# AES50.net
KiCad netlist of a schematic drawn in Altium Designer
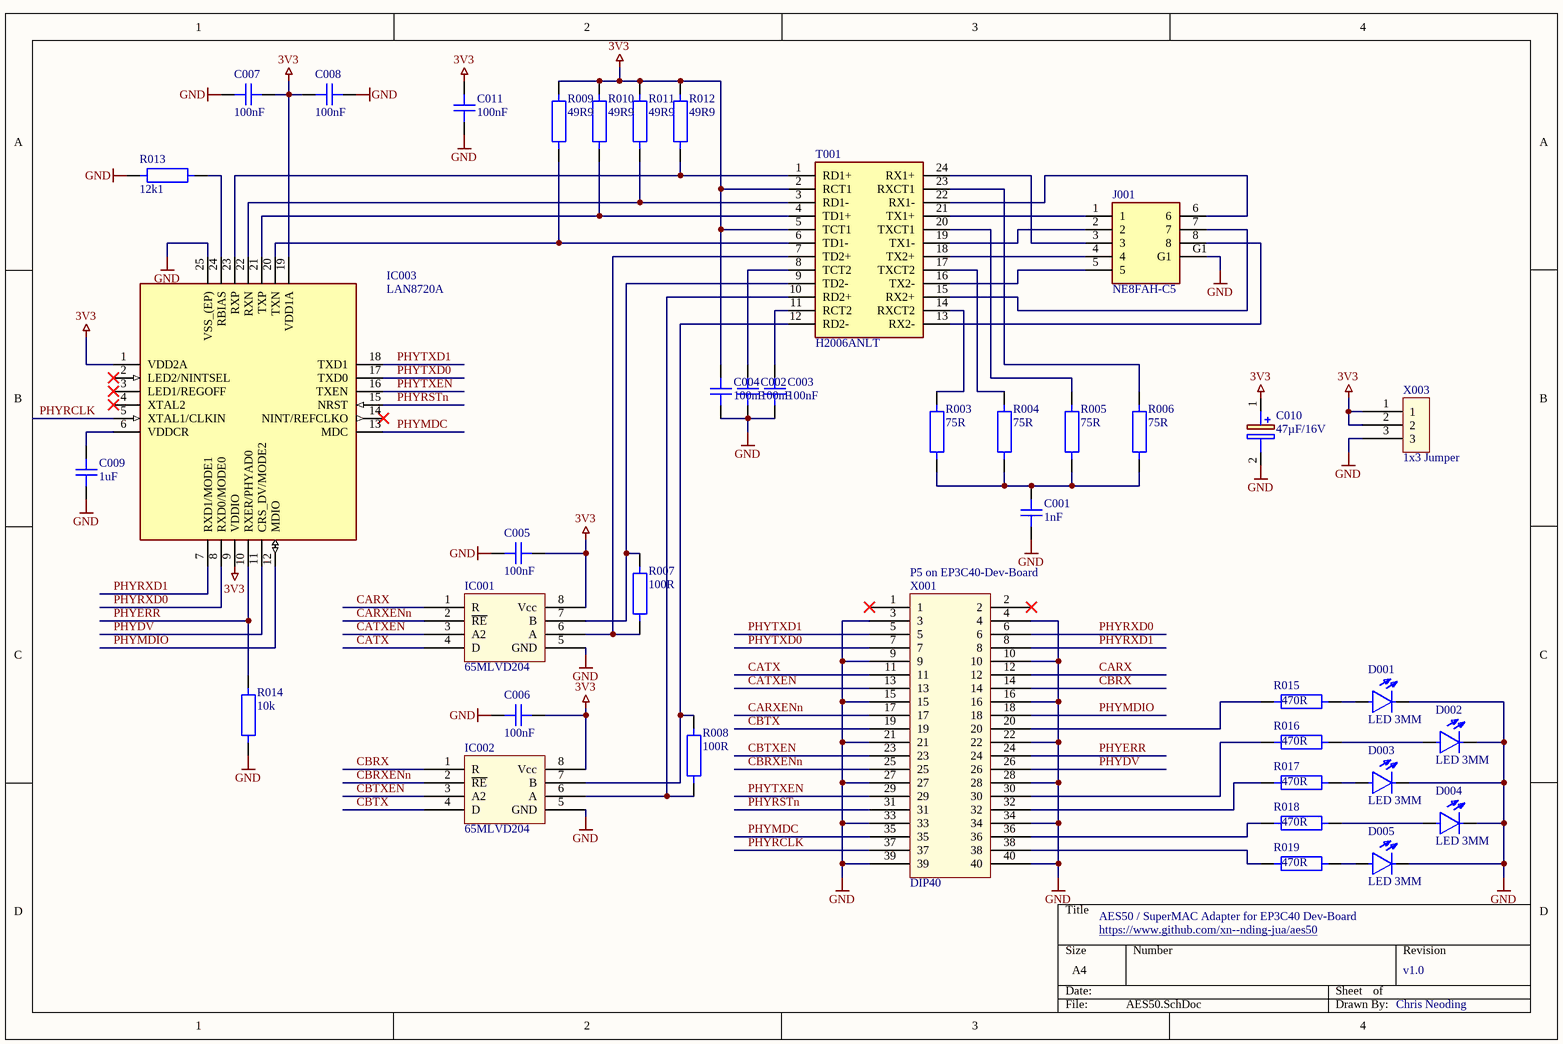
[diagram p0: AES50.SchDoc]

(export (version "E")
  (design (tool "Eeschema 10.0.6"))
  (components
    (comp (ref "C001")
      (value "1nF")
      (footprint "1206")
      (description "1206_C")
      (libsource (lib "FPGA_Board_Library") (part "1206_C_1nF/63V"))
    )
    (comp (ref "C002")
      (value "100nF")
      (footprint "1206")
      (description "1206_C")
      (libsource (lib "FPGA_Board_Library") (part "1206_C_1nF/63V"))
    )
    (comp (ref "C003")
      (value "100nF")
      (footprint "1206")
      (description "1206_C")
      (libsource (lib "FPGA_Board_Library") (part "1206_C_1nF/63V"))
    )
    (comp (ref "C004")
      (value "100nF")
      (footprint "1206")
      (description "1206_C")
      (libsource (lib "FPGA_Board_Library") (part "1206_C_1nF/63V"))
    )
    (comp (ref "C005")
      (value "100nF")
      (footprint "1206")
      (description "1206_C")
      (libsource (lib "FPGA_Board_Library") (part "1206_C_1nF/63V"))
    )
    (comp (ref "C006")
      (value "100nF")
      (footprint "1206")
      (description "1206_C")
      (libsource (lib "FPGA_Board_Library") (part "1206_C_1nF/63V"))
    )
    (comp (ref "C007")
      (value "100nF")
      (footprint "1206")
      (description "1206_C")
      (libsource (lib "FPGA_Board_Library") (part "1206_C_1nF/63V"))
    )
    (comp (ref "C008")
      (value "100nF")
      (footprint "1206")
      (description "1206_C")
      (libsource (lib "FPGA_Board_Library") (part "1206_C_1nF/63V"))
    )
    (comp (ref "C009")
      (value "1uF")
      (footprint "1206")
      (description "1206_C")
      (libsource (lib "FPGA_Board_Library") (part "1206_C_1nF/63V"))
    )
    (comp (ref "C010")
      (value "47µF/16V")
      (footprint "SamacSys:CAPPRD200W50D550H1250")
      (description "Capacitor Polarised")
      (fields (field (name "MANUFACTURER_PART_NUMBER") "MAL214256479E3"))
      (libsource (lib "SamacSys") (part "MAL214256479E3"))
    )
    (comp (ref "C011")
      (value "100nF")
      (footprint "1206")
      (description "1206_C")
      (libsource (lib "FPGA_Board_Library") (part "1206_C_1nF/63V"))
    )
    (comp (ref "D001")
      (value "LED 3MM")
      (footprint "LED 3MM")
      (libsource (lib "FPGA_Board_Library") (part "LED 3MM"))
    )
    (comp (ref "D002")
      (value "LED 3MM")
      (footprint "LED 3MM")
      (libsource (lib "FPGA_Board_Library") (part "LED 3MM"))
    )
    (comp (ref "D003")
      (value "LED 3MM")
      (footprint "LED 3MM")
      (libsource (lib "FPGA_Board_Library") (part "LED 3MM"))
    )
    (comp (ref "D004")
      (value "LED 3MM")
      (footprint "LED 3MM")
      (libsource (lib "FPGA_Board_Library") (part "LED 3MM"))
    )
    (comp (ref "D005")
      (value "LED 3MM")
      (footprint "LED 3MM")
      (libsource (lib "FPGA_Board_Library") (part "LED 3MM"))
    )
    (comp (ref "IC001")
      (value "65MLVD204")
      (footprint "SOIC-8")
      (libsource (lib "AES50_Library") (part "65MLVD204"))
    )
    (comp (ref "IC002")
      (value "65MLVD204")
      (footprint "SOIC-8")
      (libsource (lib "AES50_Library") (part "65MLVD204"))
    )
    (comp (ref "IC003")
      (value "LAN8720A")
      (footprint "SamacSys:QFN50P400X400X100-25N-D")
      (description "Integrated Circuit")
      (libsource (lib "*") (part "LAN8720A"))
    )
    (comp (ref "J001")
      (value "NE8FAH-C5")
      (footprint "SamacSys:NE8FAHC5")
      (description "Connector")
      (fields (field (name "MOUSER PART NUMBER") "568-NE8FAH-C5"))
      (libsource (lib "*") (part "NE8FAH-C5"))
    )
    (comp (ref "R003")
      (value "75R")
      (footprint "1206")
      (description "1206_R")
      (libsource (lib "FPGA_Board_Library") (part "1206_R"))
    )
    (comp (ref "R004")
      (value "75R")
      (footprint "1206")
      (description "1206_R")
      (libsource (lib "FPGA_Board_Library") (part "1206_R"))
    )
    (comp (ref "R005")
      (value "75R")
      (footprint "1206")
      (description "1206_R")
      (libsource (lib "FPGA_Board_Library") (part "1206_R"))
    )
    (comp (ref "R006")
      (value "75R")
      (footprint "1206")
      (description "1206_R")
      (libsource (lib "FPGA_Board_Library") (part "1206_R"))
    )
    (comp (ref "R007")
      (value "100R")
      (footprint "1206")
      (description "1206_R")
      (libsource (lib "FPGA_Board_Library") (part "1206_R"))
    )
    (comp (ref "R008")
      (value "100R")
      (footprint "1206")
      (description "1206_R")
      (libsource (lib "FPGA_Board_Library") (part "1206_R"))
    )
    (comp (ref "R009")
      (value "49R9")
      (footprint "1206")
      (description "1206_R")
      (libsource (lib "FPGA_Board_Library") (part "1206_R"))
    )
    (comp (ref "R010")
      (value "49R9")
      (footprint "1206")
      (description "1206_R")
      (libsource (lib "FPGA_Board_Library") (part "1206_R"))
    )
    (comp (ref "R011")
      (value "49R9")
      (footprint "1206")
      (description "1206_R")
      (libsource (lib "FPGA_Board_Library") (part "1206_R"))
    )
    (comp (ref "R012")
      (value "49R9")
      (footprint "1206")
      (description "1206_R")
      (libsource (lib "FPGA_Board_Library") (part "1206_R"))
    )
    (comp (ref "R013")
      (value "12k1")
      (footprint "1206")
      (description "1206_R")
      (libsource (lib "FPGA_Board_Library") (part "1206_R"))
    )
    (comp (ref "R014")
      (value "10k")
      (footprint "1206")
      (description "1206_R")
      (libsource (lib "FPGA_Board_Library") (part "1206_R"))
    )
    (comp (ref "R015")
      (value "470R")
      (footprint "1206")
      (description "1206_R")
      (libsource (lib "FPGA_Board_Library") (part "1206_R"))
    )
    (comp (ref "R016")
      (value "470R")
      (footprint "1206")
      (description "1206_R")
      (libsource (lib "FPGA_Board_Library") (part "1206_R"))
    )
    (comp (ref "R017")
      (value "470R")
      (footprint "1206")
      (description "1206_R")
      (libsource (lib "FPGA_Board_Library") (part "1206_R"))
    )
    (comp (ref "R018")
      (value "470R")
      (footprint "1206")
      (description "1206_R")
      (libsource (lib "FPGA_Board_Library") (part "1206_R"))
    )
    (comp (ref "R019")
      (value "470R")
      (footprint "1206")
      (description "1206_R")
      (libsource (lib "FPGA_Board_Library") (part "1206_R"))
    )
    (comp (ref "T001")
      (value "H2006ANLT")
      (footprint "SamacSys:H2006ANLT")
      (description "Transformer")
      (fields (field (name "MOUSER PART NUMBER") "673-H2006ANLT"))
      (libsource (lib "*") (part "H2006ANLT"))
    )
    (comp (ref "X001") (value "DIP40") (footprint "DIP40") (libsource (lib "AES50_Library") (part "DIP40")))
    (comp (ref "X003")
      (value "1x3 Jumper")
      (footprint "1x3 Jumper")
      (libsource (lib "KDEE_HiResPG") (part "1x3 Jumper"))
    )
  )
  (nets
    (net (code "1") (name "/CARX") (class "Default")
      (node (ref "IC001") (pin "1") (pinfunction "R_1") (pintype "passive"))
      (node (ref "X001") (pin "12") (pinfunction "12_12") (pintype "passive"))
    )
    (net (code "2") (name "/CARXENn") (class "Default")
      (node (ref "IC001") (pin "2") (pinfunction "~{RE}_2") (pintype "passive"))
      (node (ref "X001") (pin "17") (pinfunction "17_17") (pintype "passive"))
    )
    (net (code "3") (name "/CATX") (class "Default")
      (node (ref "IC001") (pin "4") (pinfunction "D_4") (pintype "passive"))
      (node (ref "X001") (pin "11") (pinfunction "11_11") (pintype "passive"))
    )
    (net (code "4") (name "/CATXEN") (class "Default")
      (node (ref "IC001") (pin "3") (pinfunction "A2_3") (pintype "passive"))
      (node (ref "X001") (pin "13") (pinfunction "13_13") (pintype "passive"))
    )
    (net (code "5") (name "/CBRX") (class "Default")
      (node (ref "IC002") (pin "1") (pinfunction "R_1") (pintype "passive"))
      (node (ref "X001") (pin "14") (pinfunction "14_14") (pintype "passive"))
    )
    (net (code "6") (name "/CBRXENn") (class "Default")
      (node (ref "IC002") (pin "2") (pinfunction "~{RE}_2") (pintype "passive"))
      (node (ref "X001") (pin "25") (pinfunction "25_25") (pintype "passive"))
    )
    (net (code "7") (name "/CBTX") (class "Default")
      (node (ref "IC002") (pin "4") (pinfunction "D_4") (pintype "passive"))
      (node (ref "X001") (pin "19") (pinfunction "19_19") (pintype "passive"))
    )
    (net (code "8") (name "/CBTXEN") (class "Default")
      (node (ref "IC002") (pin "3") (pinfunction "A2_3") (pintype "passive"))
      (node (ref "X001") (pin "23") (pinfunction "23_23") (pintype "passive"))
    )
    (net (code "9") (name "/PHYDV") (class "Default")
      (node (ref "IC003") (pin "11") (pinfunction "CRS_DV/MODE2_11") (pintype "passive"))
      (node (ref "X001") (pin "26") (pinfunction "26_26") (pintype "passive"))
    )
    (net (code "10") (name "/PHYERR") (class "Default")
      (node (ref "IC003") (pin "10") (pinfunction "RXER/PHYAD0_10") (pintype "passive"))
      (node (ref "R014") (pin "2") (pinfunction "2_2") (pintype "passive"))
      (node (ref "X001") (pin "24") (pinfunction "24_24") (pintype "passive"))
    )
    (net (code "11") (name "/PHYMDC") (class "Default")
      (node (ref "IC003") (pin "13") (pinfunction "MDC_13") (pintype "passive"))
      (node (ref "X001") (pin "35") (pinfunction "35_35") (pintype "passive"))
    )
    (net (code "12") (name "/PHYMDIO") (class "Default")
      (node (ref "IC003") (pin "12") (pinfunction "MDIO_12") (pintype "bidirectional"))
      (node (ref "X001") (pin "18") (pinfunction "18_18") (pintype "passive"))
    )
    (net (code "13") (name "/PHYRCLK") (class "Default")
      (node (ref "IC003") (pin "5") (pinfunction "XTAL1/CLKIN_5") (pintype "input"))
      (node (ref "X001") (pin "37") (pinfunction "37_37") (pintype "passive"))
    )
    (net (code "14") (name "/PHYRSTn") (class "Default")
      (node (ref "IC003") (pin "15") (pinfunction "NRST_15") (pintype "input"))
      (node (ref "X001") (pin "31") (pinfunction "31_31") (pintype "passive"))
    )
    (net (code "15") (name "/PHYRXD0") (class "Default")
      (node (ref "IC003") (pin "8") (pinfunction "RXD0/MODE0_8") (pintype "passive"))
      (node (ref "X001") (pin "6") (pinfunction "6_6") (pintype "passive"))
    )
    (net (code "16") (name "/PHYRXD1") (class "Default")
      (node (ref "IC003") (pin "7") (pinfunction "RXD1/MODE1_7") (pintype "passive"))
      (node (ref "X001") (pin "8") (pinfunction "8_8") (pintype "passive"))
    )
    (net (code "17") (name "/PHYTXD0") (class "Default")
      (node (ref "IC003") (pin "17") (pinfunction "TXD0_17") (pintype "passive"))
      (node (ref "X001") (pin "7") (pinfunction "7_7") (pintype "passive"))
    )
    (net (code "18") (name "/PHYTXD1") (class "Default")
      (node (ref "IC003") (pin "18") (pinfunction "TXD1_18") (pintype "passive"))
      (node (ref "X001") (pin "5") (pinfunction "5_5") (pintype "passive"))
    )
    (net (code "19") (name "/PHYTXEN") (class "Default")
      (node (ref "IC003") (pin "16") (pinfunction "TXEN_16") (pintype "passive"))
      (node (ref "X001") (pin "29") (pinfunction "29_29") (pintype "passive"))
    )
    (net (code "20") (name "3V3") (class "Default")
      (node (ref "C004") (pin "1") (pinfunction "1_1") (pintype "passive"))
      (node (ref "C005") (pin "1") (pinfunction "1_1") (pintype "passive"))
      (node (ref "C006") (pin "1") (pinfunction "1_1") (pintype "passive"))
      (node (ref "C007") (pin "1") (pinfunction "1_1") (pintype "passive"))
      (node (ref "C008") (pin "1") (pinfunction "1_1") (pintype "passive"))
      (node (ref "C010") (pin "1") (pinfunction "+_1") (pintype "passive"))
      (node (ref "C011") (pin "1") (pinfunction "1_1") (pintype "passive"))
      (node (ref "IC001") (pin "8") (pinfunction "Vcc_8") (pintype "passive"))
      (node (ref "IC002") (pin "8") (pinfunction "Vcc_8") (pintype "passive"))
      (node (ref "IC003") (pin "1") (pinfunction "VDD2A_1") (pintype "power_in"))
      (node (ref "IC003") (pin "19") (pinfunction "VDD1A_19") (pintype "power_in"))
      (node (ref "IC003") (pin "9") (pinfunction "VDDIO_9") (pintype "power_in"))
      (node (ref "R009") (pin "2") (pinfunction "2_2") (pintype "passive"))
      (node (ref "R010") (pin "2") (pinfunction "2_2") (pintype "passive"))
      (node (ref "R011") (pin "2") (pinfunction "2_2") (pintype "passive"))
      (node (ref "R012") (pin "2") (pinfunction "2_2") (pintype "passive"))
      (node (ref "T001") (pin "2") (pinfunction "RCT1_2") (pintype "passive"))
      (node (ref "T001") (pin "5") (pinfunction "TCT1_5") (pintype "passive"))
      (node (ref "X003") (pin "1") (pinfunction "1_1") (pintype "passive"))
      (node (ref "X003") (pin "2") (pinfunction "2_2") (pintype "passive"))
    )
    (net (code "21") (name "GND") (class "Default")
      (node (ref "C001") (pin "2") (pinfunction "2_2") (pintype "passive"))
      (node (ref "C002") (pin "2") (pinfunction "2_2") (pintype "passive"))
      (node (ref "C003") (pin "2") (pinfunction "2_2") (pintype "passive"))
      (node (ref "C004") (pin "2") (pinfunction "2_2") (pintype "passive"))
      (node (ref "C005") (pin "2") (pinfunction "2_2") (pintype "passive"))
      (node (ref "C006") (pin "2") (pinfunction "2_2") (pintype "passive"))
      (node (ref "C007") (pin "2") (pinfunction "2_2") (pintype "passive"))
      (node (ref "C008") (pin "2") (pinfunction "2_2") (pintype "passive"))
      (node (ref "C009") (pin "2") (pinfunction "2_2") (pintype "passive"))
      (node (ref "C010") (pin "2") (pinfunction "-_2") (pintype "passive"))
      (node (ref "C011") (pin "2") (pinfunction "2_2") (pintype "passive"))
      (node (ref "D001") (pin "2") (pintype "passive"))
      (node (ref "D002") (pin "2") (pintype "passive"))
      (node (ref "D003") (pin "2") (pintype "passive"))
      (node (ref "D004") (pin "2") (pintype "passive"))
      (node (ref "D005") (pin "2") (pintype "passive"))
      (node (ref "IC001") (pin "5") (pinfunction "GND_5") (pintype "passive"))
      (node (ref "IC002") (pin "5") (pinfunction "GND_5") (pintype "passive"))
      (node (ref "IC003") (pin "25") (pinfunction "VSS_(EP)_25") (pintype "power_in"))
      (node (ref "J001") (pin "G1") (pinfunction "G1_G1") (pintype "passive"))
      (node (ref "R013") (pin "1") (pinfunction "1_1") (pintype "passive"))
      (node (ref "R014") (pin "1") (pinfunction "1_1") (pintype "passive"))
      (node (ref "X001") (pin "10") (pinfunction "10_10") (pintype "passive"))
      (node (ref "X001") (pin "15") (pinfunction "15_15") (pintype "passive"))
      (node (ref "X001") (pin "16") (pinfunction "16_16") (pintype "passive"))
      (node (ref "X001") (pin "21") (pinfunction "21_21") (pintype "passive"))
      (node (ref "X001") (pin "22") (pinfunction "22_22") (pintype "passive"))
      (node (ref "X001") (pin "27") (pinfunction "27_27") (pintype "passive"))
      (node (ref "X001") (pin "28") (pinfunction "28_28") (pintype "passive"))
      (node (ref "X001") (pin "3") (pinfunction "3_3") (pintype "passive"))
      (node (ref "X001") (pin "33") (pinfunction "33_33") (pintype "passive"))
      (node (ref "X001") (pin "34") (pinfunction "34_34") (pintype "passive"))
      (node (ref "X001") (pin "39") (pinfunction "39_39") (pintype "passive"))
      (node (ref "X001") (pin "4") (pinfunction "4_4") (pintype "passive"))
      (node (ref "X001") (pin "40") (pinfunction "40_40") (pintype "passive"))
      (node (ref "X001") (pin "9") (pinfunction "9_9") (pintype "passive"))
      (node (ref "X003") (pin "3") (pinfunction "3_3") (pintype "passive"))
    )
    (net (code "22") (name "Net-(C001-Pad1)") (class "Default")
      (node (ref "C001") (pin "1") (pinfunction "1_1") (pintype "passive"))
      (node (ref "R003") (pin "1") (pinfunction "1_1") (pintype "passive"))
      (node (ref "R004") (pin "1") (pinfunction "1_1") (pintype "passive"))
      (node (ref "R005") (pin "1") (pinfunction "1_1") (pintype "passive"))
      (node (ref "R006") (pin "1") (pinfunction "1_1") (pintype "passive"))
    )
    (net (code "23") (name "Net-(D001-Pad1)") (class "Default")
      (node (ref "D001") (pin "1") (pintype "passive"))
      (node (ref "R015") (pin "1") (pinfunction "1_1") (pintype "passive"))
    )
    (net (code "24") (name "Net-(D002-Pad1)") (class "Default")
      (node (ref "D002") (pin "1") (pintype "passive"))
      (node (ref "R016") (pin "1") (pinfunction "1_1") (pintype "passive"))
    )
    (net (code "25") (name "Net-(D003-Pad1)") (class "Default")
      (node (ref "D003") (pin "1") (pintype "passive"))
      (node (ref "R017") (pin "1") (pinfunction "1_1") (pintype "passive"))
    )
    (net (code "26") (name "Net-(D004-Pad1)") (class "Default")
      (node (ref "D004") (pin "1") (pintype "passive"))
      (node (ref "R018") (pin "1") (pinfunction "1_1") (pintype "passive"))
    )
    (net (code "27") (name "Net-(D005-Pad1)") (class "Default")
      (node (ref "D005") (pin "1") (pintype "passive"))
      (node (ref "R019") (pin "1") (pinfunction "1_1") (pintype "passive"))
    )
    (net (code "28") (name "Net-(IC001-A)") (class "Default")
      (node (ref "IC001") (pin "6") (pinfunction "A_6") (pintype "passive"))
      (node (ref "R007") (pin "1") (pinfunction "1_1") (pintype "passive"))
      (node (ref "T001") (pin "7") (pinfunction "TD2+_7") (pintype "passive"))
    )
    (net (code "29") (name "Net-(IC001-B)") (class "Default")
      (node (ref "IC001") (pin "7") (pinfunction "B_7") (pintype "passive"))
      (node (ref "R007") (pin "2") (pinfunction "2_2") (pintype "passive"))
      (node (ref "T001") (pin "9") (pinfunction "TD2-_9") (pintype "passive"))
    )
    (net (code "30") (name "Net-(IC002-A)") (class "Default")
      (node (ref "IC002") (pin "6") (pinfunction "A_6") (pintype "passive"))
      (node (ref "R008") (pin "1") (pinfunction "1_1") (pintype "passive"))
      (node (ref "T001") (pin "10") (pinfunction "RD2+_10") (pintype "passive"))
    )
    (net (code "31") (name "Net-(IC002-B)") (class "Default")
      (node (ref "IC002") (pin "7") (pinfunction "B_7") (pintype "passive"))
      (node (ref "R008") (pin "2") (pinfunction "2_2") (pintype "passive"))
      (node (ref "T001") (pin "12") (pinfunction "RD2-_12") (pintype "passive"))
    )
    (net (code "32") (name "Net-(IC003-RBIAS)") (class "Default")
      (node (ref "IC003") (pin "24") (pinfunction "RBIAS_24") (pintype "passive"))
      (node (ref "R013") (pin "2") (pinfunction "2_2") (pintype "passive"))
    )
    (net (code "33") (name "Net-(IC003-RXN)") (class "Default")
      (node (ref "IC003") (pin "22") (pinfunction "RXN_22") (pintype "passive"))
      (node (ref "R011") (pin "1") (pinfunction "1_1") (pintype "passive"))
      (node (ref "T001") (pin "3") (pinfunction "RD1-_3") (pintype "passive"))
    )
    (net (code "34") (name "Net-(IC003-RXP)") (class "Default")
      (node (ref "IC003") (pin "23") (pinfunction "RXP_23") (pintype "passive"))
      (node (ref "R012") (pin "1") (pinfunction "1_1") (pintype "passive"))
      (node (ref "T001") (pin "1") (pinfunction "RD1+_1") (pintype "passive"))
    )
    (net (code "35") (name "Net-(IC003-TXN)") (class "Default")
      (node (ref "IC003") (pin "20") (pinfunction "TXN_20") (pintype "passive"))
      (node (ref "R009") (pin "1") (pinfunction "1_1") (pintype "passive"))
      (node (ref "T001") (pin "6") (pinfunction "TD1-_6") (pintype "passive"))
    )
    (net (code "36") (name "Net-(IC003-TXP)") (class "Default")
      (node (ref "IC003") (pin "21") (pinfunction "TXP_21") (pintype "passive"))
      (node (ref "R010") (pin "1") (pinfunction "1_1") (pintype "passive"))
      (node (ref "T001") (pin "4") (pinfunction "TD1+_4") (pintype "passive"))
    )
    (net (code "37") (name "Net-(IC003-VDDCR)") (class "Default")
      (node (ref "C009") (pin "1") (pinfunction "1_1") (pintype "passive"))
      (node (ref "IC003") (pin "6") (pinfunction "VDDCR_6") (pintype "power_in"))
    )
    (net (code "38") (name "Net-(R015-Pad2)") (class "Default")
      (node (ref "R015") (pin "2") (pinfunction "2_2") (pintype "passive"))
      (node (ref "X001") (pin "20") (pinfunction "20_20") (pintype "passive"))
    )
    (net (code "39") (name "Net-(R016-Pad2)") (class "Default")
      (node (ref "R016") (pin "2") (pinfunction "2_2") (pintype "passive"))
      (node (ref "X001") (pin "30") (pinfunction "30_30") (pintype "passive"))
    )
    (net (code "40") (name "Net-(R017-Pad2)") (class "Default")
      (node (ref "R017") (pin "2") (pinfunction "2_2") (pintype "passive"))
      (node (ref "X001") (pin "32") (pinfunction "32_32") (pintype "passive"))
    )
    (net (code "41") (name "Net-(R018-Pad2)") (class "Default")
      (node (ref "R018") (pin "2") (pinfunction "2_2") (pintype "passive"))
      (node (ref "X001") (pin "36") (pinfunction "36_36") (pintype "passive"))
    )
    (net (code "42") (name "Net-(R019-Pad2)") (class "Default")
      (node (ref "R019") (pin "2") (pinfunction "2_2") (pintype "passive"))
      (node (ref "X001") (pin "38") (pinfunction "38_38") (pintype "passive"))
    )
    (net (code "43") (name "Net-(T001-RCT2)") (class "Default")
      (node (ref "C003") (pin "1") (pinfunction "1_1") (pintype "passive"))
      (node (ref "T001") (pin "11") (pinfunction "RCT2_11") (pintype "passive"))
    )
    (net (code "44") (name "Net-(T001-RX1+)") (class "Default")
      (node (ref "J001") (pin "3") (pinfunction "3_3") (pintype "passive"))
      (node (ref "T001") (pin "24") (pinfunction "RX1+_24") (pintype "passive"))
    )
    (net (code "45") (name "Net-(T001-RX1-)") (class "Default")
      (node (ref "J001") (pin "6") (pinfunction "6_6") (pintype "passive"))
      (node (ref "T001") (pin "22") (pinfunction "RX1-_22") (pintype "passive"))
    )
    (net (code "46") (name "Net-(T001-RX2+)") (class "Default")
      (node (ref "J001") (pin "7") (pinfunction "7_7") (pintype "passive"))
      (node (ref "T001") (pin "15") (pinfunction "RX2+_15") (pintype "passive"))
    )
    (net (code "47") (name "Net-(T001-RX2-)") (class "Default")
      (node (ref "J001") (pin "8") (pinfunction "8_8") (pintype "passive"))
      (node (ref "T001") (pin "13") (pinfunction "RX2-_13") (pintype "passive"))
    )
    (net (code "48") (name "Net-(T001-RXCT1)") (class "Default")
      (node (ref "R006") (pin "2") (pinfunction "2_2") (pintype "passive"))
      (node (ref "T001") (pin "23") (pinfunction "RXCT1_23") (pintype "passive"))
    )
    (net (code "49") (name "Net-(T001-RXCT2)") (class "Default")
      (node (ref "R003") (pin "2") (pinfunction "2_2") (pintype "passive"))
      (node (ref "T001") (pin "14") (pinfunction "RXCT2_14") (pintype "passive"))
    )
    (net (code "50") (name "Net-(T001-TCT2)") (class "Default")
      (node (ref "C002") (pin "1") (pinfunction "1_1") (pintype "passive"))
      (node (ref "T001") (pin "8") (pinfunction "TCT2_8") (pintype "passive"))
    )
    (net (code "51") (name "Net-(T001-TX1+)") (class "Default")
      (node (ref "J001") (pin "1") (pinfunction "1_1") (pintype "passive"))
      (node (ref "T001") (pin "21") (pinfunction "TX1+_21") (pintype "passive"))
    )
    (net (code "52") (name "Net-(T001-TX1-)") (class "Default")
      (node (ref "J001") (pin "2") (pinfunction "2_2") (pintype "passive"))
      (node (ref "T001") (pin "19") (pinfunction "TX1-_19") (pintype "passive"))
    )
    (net (code "53") (name "Net-(T001-TX2+)") (class "Default")
      (node (ref "J001") (pin "4") (pinfunction "4_4") (pintype "passive"))
      (node (ref "T001") (pin "18") (pinfunction "TX2+_18") (pintype "passive"))
    )
    (net (code "54") (name "Net-(T001-TX2-)") (class "Default")
      (node (ref "J001") (pin "5") (pinfunction "5_5") (pintype "passive"))
      (node (ref "T001") (pin "16") (pinfunction "TX2-_16") (pintype "passive"))
    )
    (net (code "55") (name "Net-(T001-TXCT1)") (class "Default")
      (node (ref "R005") (pin "2") (pinfunction "2_2") (pintype "passive"))
      (node (ref "T001") (pin "20") (pinfunction "TXCT1_20") (pintype "passive"))
    )
    (net (code "56") (name "Net-(T001-TXCT2)") (class "Default")
      (node (ref "R004") (pin "2") (pinfunction "2_2") (pintype "passive"))
      (node (ref "T001") (pin "17") (pinfunction "TXCT2_17") (pintype "passive"))
    )
    (net (code "57") (name "unconnected-(IC003-LED1{slash}REGOFF-Pad3)") (class "Default")
      (node (ref "IC003") (pin "3") (pinfunction "LED1/REGOFF_3") (pintype "passive+no_connect"))
    )
    (net (code "58") (name "unconnected-(IC003-LED2{slash}NINTSEL-Pad2)") (class "Default")
      (node (ref "IC003") (pin "2") (pinfunction "LED2/NINTSEL_2") (pintype "input+no_connect"))
    )
    (net (code "59") (name "unconnected-(IC003-NINT{slash}REFCLKO-Pad14)") (class "Default")
      (node (ref "IC003") (pin "14") (pinfunction "NINT/REFCLKO_14") (pintype "output+no_connect"))
    )
    (net (code "60") (name "unconnected-(IC003-XTAL2-Pad4)") (class "Default")
      (node (ref "IC003") (pin "4") (pinfunction "XTAL2_4") (pintype "passive+no_connect"))
    )
    (net (code "61") (name "unconnected-(X001-Pad1)") (class "Default")
      (node (ref "X001") (pin "1") (pinfunction "1_1") (pintype "passive+no_connect"))
    )
    (net (code "62") (name "unconnected-(X001-Pad2)") (class "Default")
      (node (ref "X001") (pin "2") (pinfunction "2_2") (pintype "passive+no_connect"))
    )
  )
)
